# driver-power-stage-dribbler.net
KiCad netlist of a schematic drawn in Altium Designer
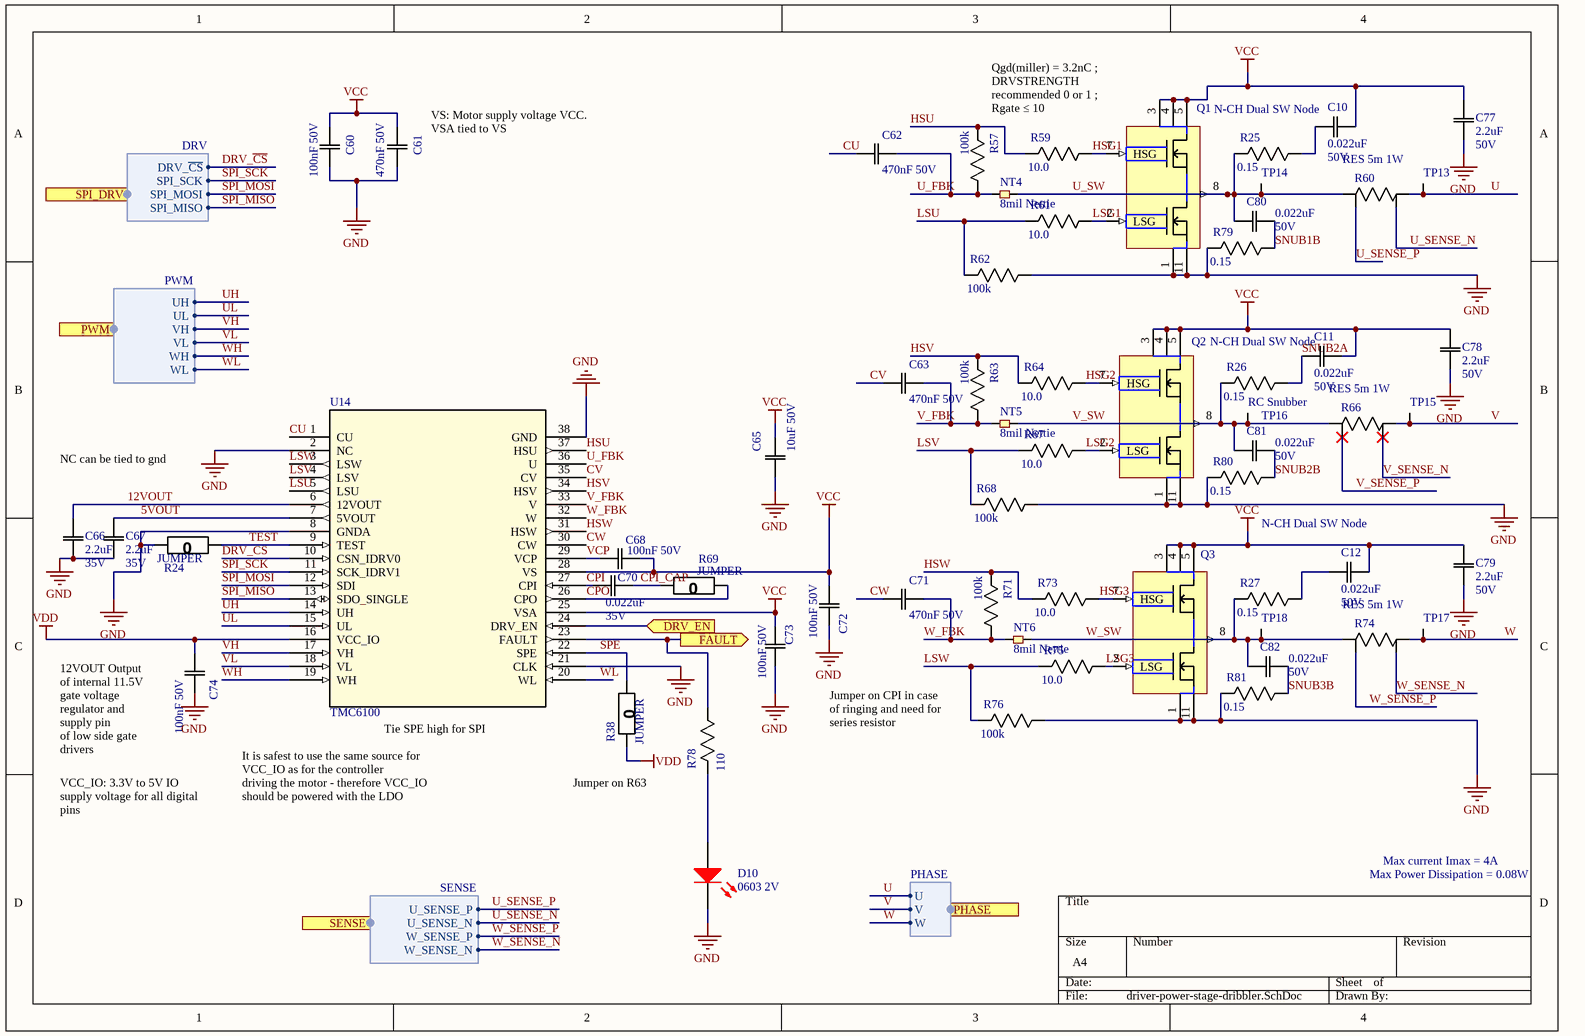
[diagram p0: driver-power-stage-dribbler.SchDoc]

(export (version "E")
  (design (tool "Eeschema 10.0.6"))
  (components
    (comp (ref "C10")
      (value "0.022uF")
      (footprint "0603")
      (description "Default Symbol for Capacitors")
      (fields
        (field (name "RATING") "50V")
        (field (name "PART NUMBER") "CAP 0.022uF 50V")
        (field (name "TOLERANCE") "10%")
      )
      (libsource (lib "capacitor_library") (part "CAP_Default"))
    )
    (comp (ref "C11")
      (value "0.022uF")
      (footprint "0603")
      (description "Default Symbol for Capacitors")
      (fields
        (field (name "RATING") "50V")
        (field (name "PART NUMBER") "CAP 0.022uF 50V")
        (field (name "TOLERANCE") "10%")
      )
      (libsource (lib "capacitor_library") (part "CAP_Default"))
    )
    (comp (ref "C12")
      (value "0.022uF")
      (footprint "0603")
      (description "Default Symbol for Capacitors")
      (fields
        (field (name "RATING") "50V")
        (field (name "PART NUMBER") "CAP 0.022uF 50V")
        (field (name "TOLERANCE") "10%")
      )
      (libsource (lib "capacitor_library") (part "CAP_Default"))
    )
    (comp (ref "C60")
      (value "100nF 50V")
      (footprint "0603")
      (description "Default Symbol for Capacitors")
      (fields (field (name "TOLERANCE") "10%") (field (name "PART NUMBER") "CAP 100nF 50V"))
      (libsource (lib "capacitor_library") (part "CAP_Default"))
    )
    (comp (ref "C61")
      (value "470nF 50V")
      (footprint "0603")
      (description "Default Symbol for Capacitors")
      (fields (field (name "TOLERANCE") "10%") (field (name "PART NUMBER") "CAP 470nF 50V"))
      (libsource (lib "capacitor_library") (part "CAP_Default"))
    )
    (comp (ref "C62")
      (value "470nF 50V")
      (footprint "0603")
      (description "Default Symbol for Capacitors")
      (fields (field (name "TOLERANCE") "10%") (field (name "PART NUMBER") "CAP 470nF 50V"))
      (libsource (lib "capacitor_library") (part "CAP_Default"))
    )
    (comp (ref "C63")
      (value "470nF 50V")
      (footprint "0603")
      (description "Default Symbol for Capacitors")
      (fields (field (name "TOLERANCE") "10%") (field (name "PART NUMBER") "CAP 470nF 50V"))
      (libsource (lib "capacitor_library") (part "CAP_Default"))
    )
    (comp (ref "C65")
      (value "10uF 50V")
      (footprint "0805")
      (description "Default Symbol for Capacitors")
      (fields (field (name "TOLERANCE") "10%") (field (name "PART NUMBER") "CAP 10uF 50V"))
      (libsource (lib "capacitor_library") (part "CAP_Default"))
    )
    (comp (ref "C66")
      (value "2.2uF")
      (footprint "0603")
      (description "Default Symbol for Capacitors")
      (fields
        (field (name "TOLERANCE") "10%")
        (field (name "RATING") "35V")
        (field (name "PART NUMBER") "CAP 2.2uF 35V")
      )
      (libsource (lib "capacitor_library") (part "CAP_Default"))
    )
    (comp (ref "C67")
      (value "2.2uF")
      (footprint "0603")
      (description "Default Symbol for Capacitors")
      (fields
        (field (name "TOLERANCE") "10%")
        (field (name "RATING") "35V")
        (field (name "PART NUMBER") "CAP 2.2uF 35V")
      )
      (libsource (lib "capacitor_library") (part "CAP_Default"))
    )
    (comp (ref "C68")
      (value "100nF 50V")
      (footprint "0603")
      (description "Default Symbol for Capacitors")
      (fields (field (name "TOLERANCE") "10%") (field (name "PART NUMBER") "CAP 100nF 50V"))
      (libsource (lib "capacitor_library") (part "CAP_Default"))
    )
    (comp (ref "C70")
      (value "0.022uF")
      (footprint "0603")
      (description "Default Symbol for Capacitors")
      (fields
        (field (name "TOLERANCE") "10%")
        (field (name "RATING") "35V")
        (field (name "PART NUMBER") "CAP 0.022uF 35V")
      )
      (libsource (lib "capacitor_library") (part "CAP_Default"))
    )
    (comp (ref "C71")
      (value "470nF 50V")
      (footprint "0603")
      (description "Default Symbol for Capacitors")
      (fields (field (name "TOLERANCE") "10%") (field (name "PART NUMBER") "CAP 470nF 50V"))
      (libsource (lib "capacitor_library") (part "CAP_Default"))
    )
    (comp (ref "C72")
      (value "100nF 50V")
      (footprint "0603")
      (description "Default Symbol for Capacitors")
      (fields (field (name "TOLERANCE") "10%") (field (name "PART NUMBER") "CAP 100nF 50V"))
      (libsource (lib "capacitor_library") (part "CAP_Default"))
    )
    (comp (ref "C73")
      (value "100nF 50V")
      (footprint "0603")
      (description "Default Symbol for Capacitors")
      (fields (field (name "TOLERANCE") "10%") (field (name "PART NUMBER") "CAP 100nF 50V"))
      (libsource (lib "capacitor_library") (part "CAP_Default"))
    )
    (comp (ref "C74")
      (value "100nF 50V")
      (footprint "0603")
      (description "Default Symbol for Capacitors")
      (fields (field (name "TOLERANCE") "10%") (field (name "PART NUMBER") "CAP 100nF 50V"))
      (libsource (lib "capacitor_library") (part "CAP_Default"))
    )
    (comp (ref "C77")
      (value "2.2uF")
      (footprint "0603")
      (description "CAP CER 2.2UF 50V X5R 0603/0805")
      (fields
        (field (name "TOLERANCE") "10%")
        (field (name "RATING") "50V")
        (field (name "PART NUMBER") "CAP 2.2uF 50V")
      )
      (libsource (lib "capacitor_library") (part "CAP 2.2uF 50V"))
    )
    (comp (ref "C78")
      (value "2.2uF")
      (footprint "0603")
      (description "CAP CER 2.2UF 50V X5R 0603/0805")
      (fields
        (field (name "TOLERANCE") "10%")
        (field (name "RATING") "50V")
        (field (name "PART NUMBER") "CAP 2.2uF 50V")
      )
      (libsource (lib "capacitor_library") (part "CAP 2.2uF 50V"))
    )
    (comp (ref "C79")
      (value "2.2uF")
      (footprint "0603")
      (description "CAP CER 2.2UF 50V X5R 0603/0805")
      (fields
        (field (name "TOLERANCE") "10%")
        (field (name "RATING") "50V")
        (field (name "PART NUMBER") "CAP 2.2uF 50V")
      )
      (libsource (lib "capacitor_library") (part "CAP 2.2uF 50V"))
    )
    (comp (ref "C80")
      (value "0.022uF")
      (footprint "0603")
      (description "Default Symbol for Capacitors")
      (fields
        (field (name "RATING") "50V")
        (field (name "PART NUMBER") "CAP 0.022uF 50V")
        (field (name "TOLERANCE") "10%")
      )
      (libsource (lib "capacitor_library") (part "CAP_Default"))
    )
    (comp (ref "C81")
      (value "0.022uF")
      (footprint "0603")
      (description "Default Symbol for Capacitors")
      (fields
        (field (name "RATING") "50V")
        (field (name "PART NUMBER") "CAP 0.022uF 50V")
        (field (name "TOLERANCE") "10%")
      )
      (libsource (lib "capacitor_library") (part "CAP_Default"))
    )
    (comp (ref "C82")
      (value "0.022uF")
      (footprint "0603")
      (description "Default Symbol for Capacitors")
      (fields
        (field (name "RATING") "50V")
        (field (name "PART NUMBER") "CAP 0.022uF 50V")
        (field (name "TOLERANCE") "10%")
      )
      (libsource (lib "capacitor_library") (part "CAP_Default"))
    )
    (comp (ref "D10")
      (value "0603 2V")
      (footprint "0603 - LED2")
      (description "0603 red led alingap 631nm-639nm water clear 18-180mcd 130d")
      (fields (field (name "PART NUMBER") "LED RED SMD 0603"))
      (libsource (lib "Diode_Library") (part "LED RED SMD 0603"))
    )
    (comp (ref "NT4")
      (value "8mil Nettie")
      (footprint "NT_8mil")
      (description "8mil wide nettie")
      (fields (field (name "PART NUMBER") "NT_8"))
      (libsource (lib "Resistor_Library") (part "NT_8"))
    )
    (comp (ref "NT5")
      (value "8mil Nettie")
      (footprint "NT_8mil")
      (description "8mil wide nettie")
      (fields (field (name "PART NUMBER") "NT_8"))
      (libsource (lib "Resistor_Library") (part "NT_8"))
    )
    (comp (ref "NT6")
      (value "8mil Nettie")
      (footprint "NT_8mil")
      (description "8mil wide nettie")
      (fields (field (name "PART NUMBER") "NT_8"))
      (libsource (lib "Resistor_Library") (part "NT_8"))
    )
    (comp (ref "Q1")
      (value "N-CH Dual SW Node")
      (footprint "12-PowerWQFN")
      (description "MOSFET N+N COMMON PHASE SW 40V 60A")
      (fields (field (name "PART NUMBER") "MOSFET N-CH DUAL NTTFD4D0N04HLTWG"))
      (libsource (lib "Transistor_Library") (part "MOSFET N-CH DUAL NTTFD4D0N04HLTWG"))
    )
    (comp (ref "Q2")
      (value "N-CH Dual SW Node")
      (footprint "12-PowerWQFN")
      (description "MOSFET N+N COMMON PHASE SW 40V 60A")
      (fields (field (name "PART NUMBER") "MOSFET N-CH DUAL NTTFD4D0N04HLTWG"))
      (libsource (lib "Transistor_Library") (part "MOSFET N-CH DUAL NTTFD4D0N04HLTWG"))
    )
    (comp (ref "Q3")
      (value "N-CH Dual SW Node")
      (footprint "12-PowerWQFN")
      (description "MOSFET N+N COMMON PHASE SW 40V 60A")
      (fields (field (name "PART NUMBER") "MOSFET N-CH DUAL NTTFD4D0N04HLTWG"))
      (libsource (lib "Transistor_Library") (part "MOSFET N-CH DUAL NTTFD4D0N04HLTWG"))
    )
    (comp (ref "R24")
      (value "JUMPER")
      (footprint "0603")
      (description "RES SMD 0 OHM JUMPER GENERIC 0805")
      (fields (field (name "PART NUMBER") "RES 0 JUMPER"))
      (libsource (lib "Resistor_Library") (part "RES 0 JUMPER"))
    )
    (comp (ref "R25")
      (value "0.15")
      (footprint "0508")
      (description "RES SMD 0.15 OHM 1% 1W 0508")
      (fields (field (name "TOLERANCE") "1%") (field (name "PART NUMBER") "RES 0.15 1W WIDE"))
      (libsource (lib "Resistor_Library") (part "RES 0.15 1W WIDE"))
    )
    (comp (ref "R26")
      (value "0.15")
      (footprint "0508")
      (description "RES SMD 0.15 OHM 1% 1W 0508")
      (fields (field (name "TOLERANCE") "1%") (field (name "PART NUMBER") "RES 0.15 1W WIDE"))
      (libsource (lib "Resistor_Library") (part "RES 0.15 1W WIDE"))
    )
    (comp (ref "R27")
      (value "0.15")
      (footprint "0508")
      (description "RES SMD 0.15 OHM 1% 1W 0508")
      (fields (field (name "TOLERANCE") "1%") (field (name "PART NUMBER") "RES 0.15 1W WIDE"))
      (libsource (lib "Resistor_Library") (part "RES 0.15 1W WIDE"))
    )
    (comp (ref "R38")
      (value "JUMPER")
      (footprint "0603")
      (description "RES SMD 0 OHM JUMPER GENERIC 0805")
      (fields (field (name "PART NUMBER") "RES 0 JUMPER"))
      (libsource (lib "Resistor_Library") (part "RES 0 JUMPER"))
    )
    (comp (ref "R57")
      (value "100k")
      (footprint "0603")
      (description "RES SMD 100K OHM 5% 1/8W 0805")
      (fields (field (name "TOLERANCE") "5%") (field (name "PART NUMBER") "RES 100k 1/8W 5%"))
      (libsource (lib "Resistor_Library") (part "RES_DEFAULT"))
    )
    (comp (ref "R59")
      (value "10.0")
      (footprint "0603")
      (description "Default Resistor Symbol")
      (fields (field (name "TOLERANCE") "1%") (field (name "PART NUMBER") "RES 10.0 1/8W - 1%"))
      (libsource (lib "Resistor_Library") (part "RES_DEFAULT"))
    )
    (comp (ref "R60")
      (value "RES 5m 1W")
      (footprint "1206 - Current Sense")
      (description "RES SMD 0.005 OHM 1% 1W 1206")
      (fields (field (name "TOLERANCE") "1%"))
      (libsource (lib "Resistor_Library") (part "RES 5m 1W"))
    )
    (comp (ref "R61")
      (value "10.0")
      (footprint "0603")
      (description "Default Resistor Symbol")
      (fields (field (name "TOLERANCE") "1%") (field (name "PART NUMBER") "RES 10.0 1/8W - 1%"))
      (libsource (lib "Resistor_Library") (part "RES_DEFAULT"))
    )
    (comp (ref "R62")
      (value "100k")
      (footprint "0603")
      (description "RES SMD 100K OHM 5% 1/8W 0805")
      (fields (field (name "TOLERANCE") "5%") (field (name "PART NUMBER") "RES 100k 1/8W 5%"))
      (libsource (lib "Resistor_Library") (part "RES_DEFAULT"))
    )
    (comp (ref "R63")
      (value "100k")
      (footprint "0603")
      (description "RES SMD 100K OHM 5% 1/8W 0805")
      (fields (field (name "TOLERANCE") "5%") (field (name "PART NUMBER") "RES 100k 1/8W 5%"))
      (libsource (lib "Resistor_Library") (part "RES_DEFAULT"))
    )
    (comp (ref "R64")
      (value "10.0")
      (footprint "0603")
      (description "Default Resistor Symbol")
      (fields (field (name "TOLERANCE") "1%") (field (name "PART NUMBER") "RES 10.0 1/8W - 1%"))
      (libsource (lib "") (part "RES_DEFAULT_1"))
    )
    (comp (ref "R66")
      (value "RES 5m 1W")
      (footprint "1206 - Current Sense")
      (description "RES SMD 0.005 OHM 1% 1W 1206")
      (fields (field (name "TOLERANCE") "1%"))
      (libsource (lib "Resistor_Library") (part "RES 5m 1W"))
    )
    (comp (ref "R67")
      (value "10.0")
      (footprint "0603")
      (description "Default Resistor Symbol")
      (fields (field (name "TOLERANCE") "1%") (field (name "PART NUMBER") "RES 10.0 1/8W - 1%"))
      (libsource (lib "Resistor_Library") (part "RES_DEFAULT"))
    )
    (comp (ref "R68")
      (value "100k")
      (footprint "0603")
      (description "RES SMD 100K OHM 5% 1/8W 0805")
      (fields (field (name "TOLERANCE") "5%") (field (name "PART NUMBER") "RES 100k 1/8W 5%"))
      (libsource (lib "Resistor_Library") (part "RES_DEFAULT"))
    )
    (comp (ref "R69")
      (value "JUMPER")
      (footprint "0603")
      (description "RES SMD 0 OHM JUMPER GENERIC 0805")
      (fields (field (name "PART NUMBER") "RES 0 JUMPER"))
      (libsource (lib "Resistor_Library") (part "RES 0 JUMPER"))
    )
    (comp (ref "R71")
      (value "100k")
      (footprint "0603")
      (description "RES SMD 100K OHM 5% 1/8W 0805")
      (fields (field (name "TOLERANCE") "5%") (field (name "PART NUMBER") "RES 100k 1/8W 5%"))
      (libsource (lib "Resistor_Library") (part "RES_DEFAULT"))
    )
    (comp (ref "R73")
      (value "10.0")
      (footprint "0603")
      (description "Default Resistor Symbol")
      (fields (field (name "TOLERANCE") "1%") (field (name "PART NUMBER") "RES 10.0 1/8W - 1%"))
      (libsource (lib "") (part "RES_DEFAULT_1"))
    )
    (comp (ref "R74")
      (value "RES 5m 1W")
      (footprint "1206 - Current Sense")
      (description "RES SMD 0.005 OHM 1% 1W 1206")
      (fields (field (name "TOLERANCE") "1%"))
      (libsource (lib "Resistor_Library") (part "RES 5m 1W"))
    )
    (comp (ref "R75")
      (value "10.0")
      (footprint "0603")
      (description "Default Resistor Symbol")
      (fields (field (name "TOLERANCE") "1%") (field (name "PART NUMBER") "RES 10.0 1/8W - 1%"))
      (libsource (lib "") (part "RES_DEFAULT_1"))
    )
    (comp (ref "R76")
      (value "100k")
      (footprint "0603")
      (description "RES SMD 100K OHM 5% 1/8W 0805")
      (fields (field (name "TOLERANCE") "5%") (field (name "PART NUMBER") "RES 100k 1/8W 5%"))
      (libsource (lib "Resistor_Library") (part "RES_DEFAULT"))
    )
    (comp (ref "R78")
      (value "110")
      (footprint "0603")
      (description "Default Resistor Symbol")
      (fields (field (name "TOLERANCE") "1%") (field (name "PART NUMBER") "RES 110.0 1/8W - 1%"))
      (libsource (lib "Resistor_Library") (part "RES_DEFAULT"))
    )
    (comp (ref "R79")
      (value "0.15")
      (footprint "0508")
      (description "RES SMD 0.15 OHM 1% 1W 0508")
      (fields (field (name "TOLERANCE") "1%") (field (name "PART NUMBER") "RES 0.15 1W WIDE"))
      (libsource (lib "") (part "RES 0.15 1W WIDE_1"))
    )
    (comp (ref "R80")
      (value "0.15")
      (footprint "0508")
      (description "RES SMD 0.15 OHM 1% 1W 0508")
      (fields (field (name "TOLERANCE") "1%") (field (name "PART NUMBER") "RES 0.15 1W WIDE"))
      (libsource (lib "") (part "RES 0.15 1W WIDE_1"))
    )
    (comp (ref "R81")
      (value "0.15")
      (footprint "0508")
      (description "RES SMD 0.15 OHM 1% 1W 0508")
      (fields (field (name "TOLERANCE") "1%") (field (name "PART NUMBER") "RES 0.15 1W WIDE"))
      (libsource (lib "") (part "RES 0.15 1W WIDE_1"))
    )
    (comp (ref "TP13")
      (value "U_SL")
      (footprint "TP")
      (fields (field (name "PART NUMBER") "Test Point (Via)"))
      (libsource (lib "IC_Library") (part "Test Point (Via)"))
    )
    (comp (ref "TP14")
      (value "U_SH")
      (footprint "TP")
      (fields (field (name "PART NUMBER") "Test Point (Via)"))
      (libsource (lib "IC_Library") (part "Test Point (Via)"))
    )
    (comp (ref "TP15")
      (value "V_SL")
      (footprint "TP")
      (fields (field (name "PART NUMBER") "Test Point (Via)"))
      (libsource (lib "IC_Library") (part "Test Point (Via)"))
    )
    (comp (ref "TP16")
      (value "V_SH")
      (footprint "TP")
      (fields (field (name "PART NUMBER") "Test Point (Via)"))
      (libsource (lib "IC_Library") (part "Test Point (Via)"))
    )
    (comp (ref "TP17")
      (value "W_SL")
      (footprint "TP")
      (fields (field (name "PART NUMBER") "Test Point (Via)"))
      (libsource (lib "IC_Library") (part "Test Point (Via)"))
    )
    (comp (ref "TP18")
      (value "W_SH")
      (footprint "TP")
      (fields (field (name "PART NUMBER") "Test Point (Via)"))
      (libsource (lib "IC_Library") (part "Test Point (Via)"))
    )
    (comp (ref "U14")
      (value "TMC6100")
      (footprint "QFN50P700X700X85_HS-38N")
      (description "GATE DRIVER IC 8-60V QFN37")
      (libsource (lib "IC_Library") (part "TMC6100"))
    )
  )
  (nets
    (net (code "5") (name "/5VOUT") (class "Default")
      (node (ref "C67") (pin "2") (pinfunction "C2_2") (pintype "passive"))
      (node (ref "U14") (pin "7") (pinfunction "5VOUT_7") (pintype "output"))
    )
    (net (code "6") (name "/12VOUT") (class "Default")
      (node (ref "C66") (pin "2") (pinfunction "C2_2") (pintype "passive"))
      (node (ref "U14") (pin "6") (pinfunction "12VOUT_6") (pintype "output"))
    )
    (net (code "7") (name "/CPI") (class "Default")
      (node (ref "C70") (pin "1") (pinfunction "C1_1") (pintype "passive"))
      (node (ref "U14") (pin "27") (pinfunction "CPI_27") (pintype "input"))
    )
    (net (code "8") (name "/CPI_CAP") (class "Default")
      (node (ref "C70") (pin "2") (pinfunction "C2_2") (pintype "passive"))
      (node (ref "R69") (pin "2") (pinfunction "R2_2") (pintype "passive"))
    )
    (net (code "9") (name "/CPO") (class "Default")
      (node (ref "R69") (pin "1") (pinfunction "R1_1") (pintype "passive"))
      (node (ref "U14") (pin "26") (pinfunction "CPO_26") (pintype "output"))
    )
    (net (code "10") (name "/CU") (class "Default")
      (node (ref "C62") (pin "1") (pinfunction "C1_1") (pintype "passive"))
      (node (ref "U14") (pin "1") (pinfunction "CU_1") (pintype "passive"))
    )
    (net (code "11") (name "/CV") (class "Default")
      (node (ref "C63") (pin "1") (pinfunction "C1_1") (pintype "passive"))
      (node (ref "U14") (pin "35") (pinfunction "CV_35") (pintype "passive"))
    )
    (net (code "12") (name "/CW") (class "Default")
      (node (ref "C71") (pin "1") (pinfunction "C1_1") (pintype "passive"))
      (node (ref "U14") (pin "30") (pinfunction "CW_30") (pintype "passive"))
    )
    (net (code "13") (name "/DRV_EN") (class "Default")
      (node (ref "U14") (pin "24") (pinfunction "DRV_EN_24") (pintype "input"))
    )
    (net (code "14") (name "/DRV_~{CS}") (class "Default")
      (node (ref "U14") (pin "10") (pinfunction "CSN_IDRV0_10") (pintype "input"))
    )
    (net (code "15") (name "/FAULT") (class "Default")
      (node (ref "R78") (pin "1") (pinfunction "R1_1") (pintype "passive"))
      (node (ref "U14") (pin "23") (pinfunction "FAULT_23") (pintype "output"))
    )
    (net (code "16") (name "/HSG1") (class "Default")
      (node (ref "Q1") (pin "7") (pinfunction "HSG_7") (pintype "input"))
      (node (ref "R59") (pin "1") (pinfunction "R1_1") (pintype "passive"))
    )
    (net (code "17") (name "/HSG2") (class "Default")
      (node (ref "Q2") (pin "7") (pinfunction "HSG_7") (pintype "input"))
      (node (ref "R64") (pin "1") (pinfunction "R1_1") (pintype "passive"))
    )
    (net (code "18") (name "/HSG3") (class "Default")
      (node (ref "Q3") (pin "7") (pinfunction "HSG_7") (pintype "input"))
      (node (ref "R73") (pin "1") (pinfunction "R1_1") (pintype "passive"))
    )
    (net (code "19") (name "/HSU") (class "Default")
      (node (ref "R57") (pin "2") (pinfunction "R2_2") (pintype "passive"))
      (node (ref "R59") (pin "2") (pinfunction "R2_2") (pintype "passive"))
      (node (ref "U14") (pin "37") (pinfunction "HSU_37") (pintype "output"))
    )
    (net (code "20") (name "/HSV") (class "Default")
      (node (ref "R63") (pin "2") (pinfunction "R2_2") (pintype "passive"))
      (node (ref "R64") (pin "2") (pinfunction "R2_2") (pintype "passive"))
      (node (ref "U14") (pin "34") (pinfunction "HSV_34") (pintype "output"))
    )
    (net (code "21") (name "/HSW") (class "Default")
      (node (ref "R71") (pin "2") (pinfunction "R2_2") (pintype "passive"))
      (node (ref "R73") (pin "2") (pinfunction "R2_2") (pintype "passive"))
      (node (ref "U14") (pin "31") (pinfunction "HSW_31") (pintype "output"))
    )
    (net (code "22") (name "/LSG1") (class "Default")
      (node (ref "Q1") (pin "2") (pinfunction "LSG_2") (pintype "input"))
      (node (ref "R61") (pin "1") (pinfunction "R1_1") (pintype "passive"))
    )
    (net (code "23") (name "/LSG2") (class "Default")
      (node (ref "Q2") (pin "2") (pinfunction "LSG_2") (pintype "input"))
      (node (ref "R67") (pin "1") (pinfunction "R1_1") (pintype "passive"))
    )
    (net (code "24") (name "/LSG3") (class "Default")
      (node (ref "Q3") (pin "2") (pinfunction "LSG_2") (pintype "input"))
      (node (ref "R75") (pin "1") (pinfunction "R1_1") (pintype "passive"))
    )
    (net (code "25") (name "/LSU") (class "Default")
      (node (ref "R61") (pin "2") (pinfunction "R2_2") (pintype "passive"))
      (node (ref "R62") (pin "2") (pinfunction "R2_2") (pintype "passive"))
      (node (ref "U14") (pin "5") (pinfunction "LSU_5") (pintype "output"))
    )
    (net (code "26") (name "/LSV") (class "Default")
      (node (ref "R67") (pin "2") (pinfunction "R2_2") (pintype "passive"))
      (node (ref "R68") (pin "2") (pinfunction "R2_2") (pintype "passive"))
      (node (ref "U14") (pin "4") (pinfunction "LSV_4") (pintype "output"))
    )
    (net (code "27") (name "/LSW") (class "Default")
      (node (ref "R75") (pin "2") (pinfunction "R2_2") (pintype "passive"))
      (node (ref "R76") (pin "2") (pinfunction "R2_2") (pintype "passive"))
      (node (ref "U14") (pin "3") (pinfunction "LSW_3") (pintype "output"))
    )
    (net (code "28") (name "/SNUB1B") (class "Default")
      (node (ref "C80") (pin "2") (pinfunction "C2_2") (pintype "passive"))
      (node (ref "R79") (pin "1") (pinfunction "R1_1") (pintype "passive"))
    )
    (net (code "29") (name "/SNUB2A") (class "Default")
      (node (ref "C11") (pin "1") (pinfunction "C1_1") (pintype "passive"))
      (node (ref "R26") (pin "1") (pinfunction "R1_1") (pintype "passive"))
    )
    (net (code "30") (name "/SNUB2B") (class "Default")
      (node (ref "C81") (pin "2") (pinfunction "C2_2") (pintype "passive"))
      (node (ref "R80") (pin "1") (pinfunction "R1_1") (pintype "passive"))
    )
    (net (code "31") (name "/SNUB3B") (class "Default")
      (node (ref "C82") (pin "2") (pinfunction "C2_2") (pintype "passive"))
      (node (ref "R81") (pin "1") (pinfunction "R1_1") (pintype "passive"))
    )
    (net (code "32") (name "/SPE") (class "Default")
      (node (ref "R38") (pin "1") (pinfunction "R1_1") (pintype "passive"))
      (node (ref "U14") (pin "22") (pinfunction "SPE_22") (pintype "input"))
    )
    (net (code "33") (name "/SPI_MISO") (class "Default")
      (node (ref "U14") (pin "13") (pinfunction "SDO_SINGLE_13") (pintype "bidirectional"))
    )
    (net (code "34") (name "/SPI_MOSI") (class "Default")
      (node (ref "U14") (pin "12") (pinfunction "SDI_12") (pintype "input"))
    )
    (net (code "35") (name "/SPI_SCK") (class "Default")
      (node (ref "U14") (pin "11") (pinfunction "SCK_IDRV1_11") (pintype "input"))
    )
    (net (code "36") (name "/TEST") (class "Default")
      (node (ref "R24") (pin "1") (pinfunction "R1_1") (pintype "passive"))
      (node (ref "U14") (pin "9") (pinfunction "TEST_9") (pintype "input"))
    )
    (net (code "37") (name "/U") (class "Default")
      (node (ref "R60") (pin "2") (pinfunction "2_2") (pintype "passive"))
      (node (ref "TP13") (pin "1") (pinfunction "1_1") (pintype "passive"))
    )
    (net (code "38") (name "/UH") (class "Default")
      (node (ref "U14") (pin "14") (pinfunction "UH_14") (pintype "input"))
    )
    (net (code "39") (name "/UL") (class "Default")
      (node (ref "U14") (pin "15") (pinfunction "UL_15") (pintype "input"))
    )
    (net (code "40") (name "/U_FBK") (class "Default")
      (node (ref "C62") (pin "2") (pinfunction "C2_2") (pintype "passive"))
      (node (ref "NT4") (pin "1") (pinfunction "1_1") (pintype "passive"))
      (node (ref "R57") (pin "1") (pinfunction "R1_1") (pintype "passive"))
      (node (ref "U14") (pin "36") (pinfunction "U_36") (pintype "passive"))
    )
    (net (code "41") (name "/U_SENSE_N") (class "Default")
      (node (ref "R60") (pin "S2") (pinfunction "S2_S2") (pintype "passive"))
    )
    (net (code "42") (name "/U_SENSE_P") (class "Default")
      (node (ref "R60") (pin "S1") (pinfunction "S1_S1") (pintype "passive"))
    )
    (net (code "43") (name "/U_SW") (class "Default")
      (node (ref "C80") (pin "1") (pinfunction "C1_1") (pintype "passive"))
      (node (ref "NT4") (pin "2") (pinfunction "2_2") (pintype "passive"))
      (node (ref "Q1") (pin "8") (pinfunction "SW_8") (pintype "output"))
      (node (ref "R25") (pin "2") (pinfunction "R2_2") (pintype "passive"))
      (node (ref "R60") (pin "1") (pinfunction "1_1") (pintype "passive"))
      (node (ref "TP14") (pin "1") (pinfunction "1_1") (pintype "passive"))
    )
    (net (code "44") (name "/V") (class "Default")
      (node (ref "R66") (pin "2") (pinfunction "2_2") (pintype "passive"))
      (node (ref "TP15") (pin "1") (pinfunction "1_1") (pintype "passive"))
    )
    (net (code "45") (name "/VCP") (class "Default")
      (node (ref "C68") (pin "1") (pinfunction "C1_1") (pintype "passive"))
      (node (ref "U14") (pin "29") (pinfunction "VCP_29") (pintype "power_in"))
    )
    (net (code "46") (name "/VH") (class "Default")
      (node (ref "U14") (pin "17") (pinfunction "VH_17") (pintype "input"))
    )
    (net (code "47") (name "/VL") (class "Default")
      (node (ref "U14") (pin "18") (pinfunction "VL_18") (pintype "input"))
    )
    (net (code "48") (name "/V_FBK") (class "Default")
      (node (ref "C63") (pin "2") (pinfunction "C2_2") (pintype "passive"))
      (node (ref "NT5") (pin "1") (pinfunction "1_1") (pintype "passive"))
      (node (ref "R63") (pin "1") (pinfunction "R1_1") (pintype "passive"))
      (node (ref "U14") (pin "33") (pinfunction "V_33") (pintype "passive"))
    )
    (net (code "49") (name "/V_SENSE_N") (class "Default")
      (node (ref "R66") (pin "S2") (pinfunction "S2_S2") (pintype "passive+no_connect"))
    )
    (net (code "50") (name "/V_SENSE_P") (class "Default")
      (node (ref "R66") (pin "S1") (pinfunction "S1_S1") (pintype "passive+no_connect"))
    )
    (net (code "51") (name "/V_SW") (class "Default")
      (node (ref "C81") (pin "1") (pinfunction "C1_1") (pintype "passive"))
      (node (ref "NT5") (pin "2") (pinfunction "2_2") (pintype "passive"))
      (node (ref "Q2") (pin "8") (pinfunction "SW_8") (pintype "output"))
      (node (ref "R26") (pin "2") (pinfunction "R2_2") (pintype "passive"))
      (node (ref "R66") (pin "1") (pinfunction "1_1") (pintype "passive"))
      (node (ref "TP16") (pin "1") (pinfunction "1_1") (pintype "passive"))
    )
    (net (code "52") (name "/W") (class "Default")
      (node (ref "R74") (pin "2") (pinfunction "2_2") (pintype "passive"))
      (node (ref "TP17") (pin "1") (pinfunction "1_1") (pintype "passive"))
    )
    (net (code "53") (name "/WH") (class "Default")
      (node (ref "U14") (pin "19") (pinfunction "WH_19") (pintype "input"))
    )
    (net (code "54") (name "/WL") (class "Default")
      (node (ref "U14") (pin "20") (pinfunction "WL_20") (pintype "input"))
    )
    (net (code "55") (name "/W_FBK") (class "Default")
      (node (ref "C71") (pin "2") (pinfunction "C2_2") (pintype "passive"))
      (node (ref "NT6") (pin "1") (pinfunction "1_1") (pintype "passive"))
      (node (ref "R71") (pin "1") (pinfunction "R1_1") (pintype "passive"))
      (node (ref "U14") (pin "32") (pinfunction "W_32") (pintype "passive"))
    )
    (net (code "56") (name "/W_SENSE_N") (class "Default")
      (node (ref "R74") (pin "S2") (pinfunction "S2_S2") (pintype "passive"))
    )
    (net (code "57") (name "/W_SENSE_P") (class "Default")
      (node (ref "R74") (pin "S1") (pinfunction "S1_S1") (pintype "passive"))
    )
    (net (code "58") (name "/W_SW") (class "Default")
      (node (ref "C82") (pin "1") (pinfunction "C1_1") (pintype "passive"))
      (node (ref "NT6") (pin "2") (pinfunction "2_2") (pintype "passive"))
      (node (ref "Q3") (pin "8") (pinfunction "SW_8") (pintype "output"))
      (node (ref "R27") (pin "2") (pinfunction "R2_2") (pintype "passive"))
      (node (ref "R74") (pin "1") (pinfunction "1_1") (pintype "passive"))
      (node (ref "TP18") (pin "1") (pinfunction "1_1") (pintype "passive"))
    )
    (net (code "63") (name "GND") (class "Default")
      (node (ref "C60") (pin "2") (pinfunction "C2_2") (pintype "passive"))
      (node (ref "C61") (pin "2") (pinfunction "C2_2") (pintype "passive"))
      (node (ref "C65") (pin "1") (pinfunction "C1_1") (pintype "passive"))
      (node (ref "C66") (pin "1") (pinfunction "C1_1") (pintype "passive"))
      (node (ref "C67") (pin "1") (pinfunction "C1_1") (pintype "passive"))
      (node (ref "C72") (pin "2") (pinfunction "C2_2") (pintype "passive"))
      (node (ref "C73") (pin "2") (pinfunction "C2_2") (pintype "passive"))
      (node (ref "C74") (pin "2") (pinfunction "C2_2") (pintype "passive"))
      (node (ref "C77") (pin "1") (pinfunction "C1_1") (pintype "passive"))
      (node (ref "C78") (pin "1") (pinfunction "C1_1") (pintype "passive"))
      (node (ref "C79") (pin "1") (pinfunction "C1_1") (pintype "passive"))
      (node (ref "D10") (pin "2") (pinfunction "K_2") (pintype "passive"))
      (node (ref "Q1") (pin "1") (pinfunction "GND_1") (pintype "power_in"))
      (node (ref "Q1") (pin "11") (pinfunction "GND_11") (pintype "power_in"))
      (node (ref "Q2") (pin "1") (pinfunction "GND_1") (pintype "power_in"))
      (node (ref "Q2") (pin "11") (pinfunction "GND_11") (pintype "power_in"))
      (node (ref "Q3") (pin "1") (pinfunction "GND_1") (pintype "power_in"))
      (node (ref "Q3") (pin "11") (pinfunction "GND_11") (pintype "power_in"))
      (node (ref "R24") (pin "2") (pinfunction "R2_2") (pintype "passive"))
      (node (ref "R62") (pin "1") (pinfunction "R1_1") (pintype "passive"))
      (node (ref "R68") (pin "1") (pinfunction "R1_1") (pintype "passive"))
      (node (ref "R76") (pin "1") (pinfunction "R1_1") (pintype "passive"))
      (node (ref "R79") (pin "2") (pinfunction "R2_2") (pintype "passive"))
      (node (ref "R80") (pin "2") (pinfunction "R2_2") (pintype "passive"))
      (node (ref "R81") (pin "2") (pinfunction "R2_2") (pintype "passive"))
      (node (ref "U14") (pin "2") (pinfunction "NC_2") (pintype "passive"))
      (node (ref "U14") (pin "21") (pinfunction "CLK_21") (pintype "input"))
      (node (ref "U14") (pin "38") (pinfunction "GND_38") (pintype "passive"))
      (node (ref "U14") (pin "8") (pinfunction "GNDA_8") (pintype "power_in"))
    )
    (net (code "64") (name "Net-(C10-C1)") (class "Default")
      (node (ref "C10") (pin "1") (pinfunction "C1_1") (pintype "passive"))
      (node (ref "R25") (pin "1") (pinfunction "R1_1") (pintype "passive"))
    )
    (net (code "65") (name "Net-(C12-C1)") (class "Default")
      (node (ref "C12") (pin "1") (pinfunction "C1_1") (pintype "passive"))
      (node (ref "R27") (pin "1") (pinfunction "R1_1") (pintype "passive"))
    )
    (net (code "66") (name "Net-(D10-A)") (class "Default")
      (node (ref "D10") (pin "1") (pinfunction "A_1") (pintype "passive"))
      (node (ref "R78") (pin "2") (pinfunction "R2_2") (pintype "passive"))
    )
    (net (code "67") (name "VCC") (class "Default")
      (node (ref "C10") (pin "2") (pinfunction "C2_2") (pintype "passive"))
      (node (ref "C11") (pin "2") (pinfunction "C2_2") (pintype "passive"))
      (node (ref "C12") (pin "2") (pinfunction "C2_2") (pintype "passive"))
      (node (ref "C60") (pin "1") (pinfunction "C1_1") (pintype "passive"))
      (node (ref "C61") (pin "1") (pinfunction "C1_1") (pintype "passive"))
      (node (ref "C65") (pin "2") (pinfunction "C2_2") (pintype "passive"))
      (node (ref "C68") (pin "2") (pinfunction "C2_2") (pintype "passive"))
      (node (ref "C72") (pin "1") (pinfunction "C1_1") (pintype "passive"))
      (node (ref "C73") (pin "1") (pinfunction "C1_1") (pintype "passive"))
      (node (ref "C77") (pin "2") (pinfunction "C2_2") (pintype "passive"))
      (node (ref "C78") (pin "2") (pinfunction "C2_2") (pintype "passive"))
      (node (ref "C79") (pin "2") (pinfunction "C2_2") (pintype "passive"))
      (node (ref "Q1") (pin "3") (pinfunction "V+_3") (pintype "power_in"))
      (node (ref "Q1") (pin "4") (pinfunction "V+_4") (pintype "power_in"))
      (node (ref "Q1") (pin "5") (pinfunction "V+_5") (pintype "power_in"))
      (node (ref "Q2") (pin "3") (pinfunction "V+_3") (pintype "power_in"))
      (node (ref "Q2") (pin "4") (pinfunction "V+_4") (pintype "power_in"))
      (node (ref "Q2") (pin "5") (pinfunction "V+_5") (pintype "power_in"))
      (node (ref "Q3") (pin "3") (pinfunction "V+_3") (pintype "power_in"))
      (node (ref "Q3") (pin "4") (pinfunction "V+_4") (pintype "power_in"))
      (node (ref "Q3") (pin "5") (pinfunction "V+_5") (pintype "power_in"))
      (node (ref "U14") (pin "25") (pinfunction "VSA_25") (pintype "power_in"))
      (node (ref "U14") (pin "28") (pinfunction "VS_28") (pintype "power_in"))
    )
    (net (code "68") (name "VDD") (class "Default")
      (node (ref "C74") (pin "1") (pinfunction "C1_1") (pintype "passive"))
      (node (ref "R38") (pin "2") (pinfunction "R2_2") (pintype "passive"))
      (node (ref "U14") (pin "16") (pinfunction "VCC_IO_16") (pintype "power_in"))
    )
  )
)
